# BrauV2_AnalogueInput.net
KiCad netlist of a schematic drawn in Altium Designer
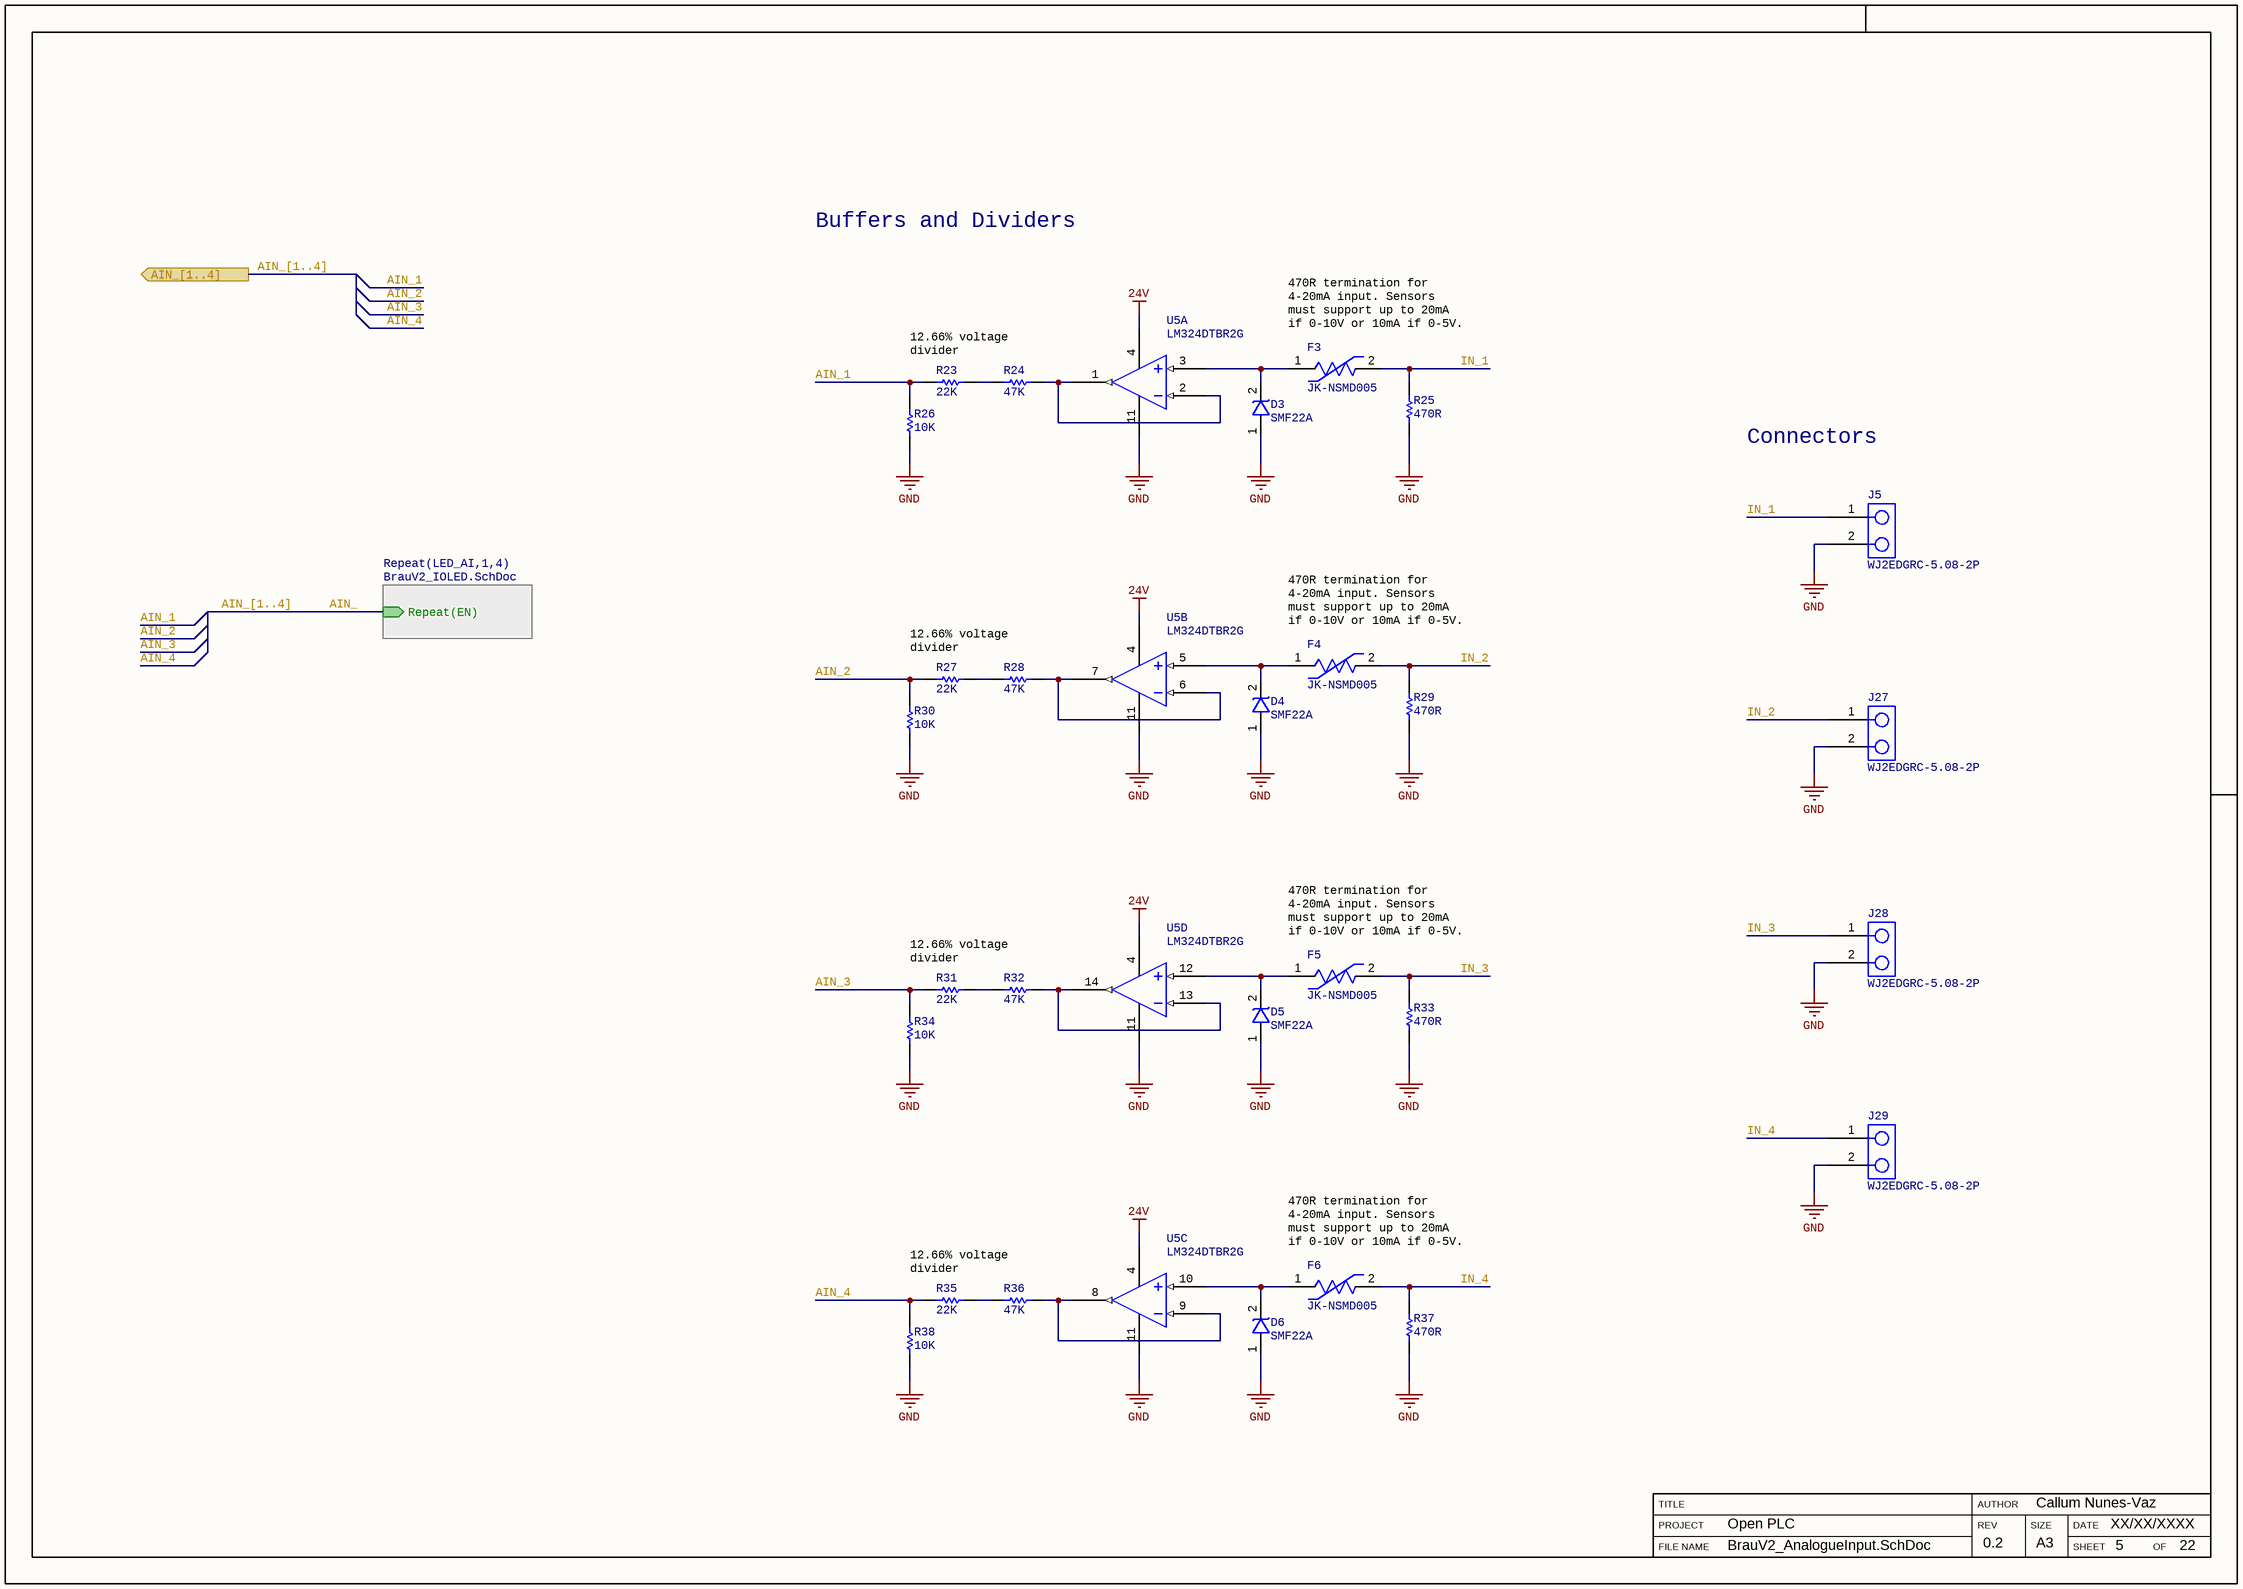
[diagram p0: BrauV2_AnalogueInput.SchDoc]

(export (version "E")
  (design (tool "Eeschema 10.0.6"))
  (components
    (comp (ref "D3")
      (value "SMF22A")
      (footprint "SOD-123FL")
      (description "Unidirectional 22V 24.4V 35.5V 5.6A SOD-123F TVS RoHS")
      (libsource (lib "BrauV2") (part "SMF22A"))
    )
    (comp (ref "D4")
      (value "SMF22A")
      (footprint "SOD-123FL")
      (description "Unidirectional 22V 24.4V 35.5V 5.6A SOD-123F TVS RoHS")
      (libsource (lib "BrauV2") (part "SMF22A"))
    )
    (comp (ref "D5")
      (value "SMF22A")
      (footprint "SOD-123FL")
      (description "Unidirectional 22V 24.4V 35.5V 5.6A SOD-123F TVS RoHS")
      (libsource (lib "BrauV2") (part "SMF22A"))
    )
    (comp (ref "D6")
      (value "SMF22A")
      (footprint "SOD-123FL")
      (description "Unidirectional 22V 24.4V 35.5V 5.6A SOD-123F TVS RoHS")
      (libsource (lib "BrauV2") (part "SMF22A"))
    )
    (comp (ref "F3")
      (value "JK-NSMD005")
      (footprint "SMD_RES_1206(3216)_N")
      (description "60V 150mA 1.5s 1206 PTC Resettable Fuses RoHS")
      (libsource (lib "BrauV2_Resistor") (part "JK-NSMD005"))
    )
    (comp (ref "F4")
      (value "JK-NSMD005")
      (footprint "SMD_RES_1206(3216)_N")
      (description "60V 150mA 1.5s 1206 PTC Resettable Fuses RoHS")
      (libsource (lib "BrauV2_Resistor") (part "JK-NSMD005"))
    )
    (comp (ref "F5")
      (value "JK-NSMD005")
      (footprint "SMD_RES_1206(3216)_N")
      (description "60V 150mA 1.5s 1206 PTC Resettable Fuses RoHS")
      (libsource (lib "BrauV2_Resistor") (part "JK-NSMD005"))
    )
    (comp (ref "F6")
      (value "JK-NSMD005")
      (footprint "SMD_RES_1206(3216)_N")
      (description "60V 150mA 1.5s 1206 PTC Resettable Fuses RoHS")
      (libsource (lib "BrauV2_Resistor") (part "JK-NSMD005"))
    )
    (comp (ref "J5")
      (value "WJ2EDGRC-5.08-2P")
      (footprint "796638-2")
      (description "Covered（4Sided） 2 1 0.200\"（5.08mm） 2 P=5.08mm Pluggable System Terminal Block RoHS")
      (libsource (lib "BrauV2_Connector") (part "WJ2EDGRC-5.08-2P"))
    )
    (comp (ref "J27")
      (value "WJ2EDGRC-5.08-2P")
      (footprint "796638-2")
      (description "Covered（4Sided） 2 1 0.200\"（5.08mm） 2 P=5.08mm Pluggable System Terminal Block RoHS")
      (libsource (lib "BrauV2_Connector") (part "WJ2EDGRC-5.08-2P"))
    )
    (comp (ref "J28")
      (value "WJ2EDGRC-5.08-2P")
      (footprint "796638-2")
      (description "Covered（4Sided） 2 1 0.200\"（5.08mm） 2 P=5.08mm Pluggable System Terminal Block RoHS")
      (libsource (lib "BrauV2_Connector") (part "WJ2EDGRC-5.08-2P"))
    )
    (comp (ref "J29")
      (value "WJ2EDGRC-5.08-2P")
      (footprint "796638-2")
      (description "Covered（4Sided） 2 1 0.200\"（5.08mm） 2 P=5.08mm Pluggable System Terminal Block RoHS")
      (libsource (lib "BrauV2_Connector") (part "WJ2EDGRC-5.08-2P"))
    )
    (comp (ref "R23")
      (value "RC0402FR-0722KL")
      (footprint "SMD_RES_0402(1005)_N")
      (description "22kΩ ±1% 1/16W ±100ppm/℃ 0402 Chip Resistor - Surface Mount RoHS")
      (fields (field (name "TOLERANCE") "1%") (field (name "RESISTANCE") "22K"))
      (libsource (lib "BrauV2_Resistor") (part "22K 0402 1% 1/16W"))
    )
    (comp (ref "R24")
      (value "RC0402FR-0747KL")
      (footprint "SMD_RES_0402(1005)_N")
      (description "47kΩ ±1% 1/16W ±100ppm/℃ 0402 Chip Resistor - Surface Mount RoHS")
      (fields (field (name "TOLERANCE") "1%") (field (name "RESISTANCE") "47K"))
      (libsource (lib "BrauV2_Resistor") (part "47K 0402 1% 1/16W"))
    )
    (comp (ref "R25")
      (value "AC2512FK-07470RL")
      (footprint "SMD_RES_2512(6432)_N")
      (description "470Ω ±1% 1W ±100ppm/℃ 2512 Chip Resistor - Surface Mount RoHS")
      (fields (field (name "TOLERANCE") "1%") (field (name "RESISTANCE") "470R"))
      (libsource (lib "BrauV2_Resistor") (part "470R 2512 1% 1W"))
    )
    (comp (ref "R26")
      (value "RC0402FR-0710KL")
      (footprint "SMD_RES_0402(1005)_N")
      (description "10kΩ ±1% 1/16W ±100ppm/℃ 0402 Chip Resistor - Surface Mount RoHS")
      (fields (field (name "TOLERANCE") "1%") (field (name "RESISTANCE") "10K"))
      (libsource (lib "BrauV2_Resistor") (part "10K 0402 1% 1/16W"))
    )
    (comp (ref "R27")
      (value "RC0402FR-0722KL")
      (footprint "SMD_RES_0402(1005)_N")
      (description "22kΩ ±1% 1/16W ±100ppm/℃ 0402 Chip Resistor - Surface Mount RoHS")
      (fields (field (name "TOLERANCE") "1%") (field (name "RESISTANCE") "22K"))
      (libsource (lib "BrauV2_Resistor") (part "22K 0402 1% 1/16W"))
    )
    (comp (ref "R28")
      (value "RC0402FR-0747KL")
      (footprint "SMD_RES_0402(1005)_N")
      (description "47kΩ ±1% 1/16W ±100ppm/℃ 0402 Chip Resistor - Surface Mount RoHS")
      (fields (field (name "TOLERANCE") "1%") (field (name "RESISTANCE") "47K"))
      (libsource (lib "BrauV2_Resistor") (part "47K 0402 1% 1/16W"))
    )
    (comp (ref "R29")
      (value "AC2512FK-07470RL")
      (footprint "SMD_RES_2512(6432)_N")
      (description "470Ω ±1% 1W ±100ppm/℃ 2512 Chip Resistor - Surface Mount RoHS")
      (fields (field (name "TOLERANCE") "1%") (field (name "RESISTANCE") "470R"))
      (libsource (lib "BrauV2_Resistor") (part "470R 2512 1% 1W"))
    )
    (comp (ref "R30")
      (value "RC0402FR-0710KL")
      (footprint "SMD_RES_0402(1005)_N")
      (description "10kΩ ±1% 1/16W ±100ppm/℃ 0402 Chip Resistor - Surface Mount RoHS")
      (fields (field (name "TOLERANCE") "1%") (field (name "RESISTANCE") "10K"))
      (libsource (lib "BrauV2_Resistor") (part "10K 0402 1% 1/16W"))
    )
    (comp (ref "R31")
      (value "RC0402FR-0722KL")
      (footprint "SMD_RES_0402(1005)_N")
      (description "22kΩ ±1% 1/16W ±100ppm/℃ 0402 Chip Resistor - Surface Mount RoHS")
      (fields (field (name "TOLERANCE") "1%") (field (name "RESISTANCE") "22K"))
      (libsource (lib "BrauV2_Resistor") (part "22K 0402 1% 1/16W"))
    )
    (comp (ref "R32")
      (value "RC0402FR-0747KL")
      (footprint "SMD_RES_0402(1005)_N")
      (description "47kΩ ±1% 1/16W ±100ppm/℃ 0402 Chip Resistor - Surface Mount RoHS")
      (fields (field (name "TOLERANCE") "1%") (field (name "RESISTANCE") "47K"))
      (libsource (lib "BrauV2_Resistor") (part "47K 0402 1% 1/16W"))
    )
    (comp (ref "R33")
      (value "AC2512FK-07470RL")
      (footprint "SMD_RES_2512(6432)_N")
      (description "470Ω ±1% 1W ±100ppm/℃ 2512 Chip Resistor - Surface Mount RoHS")
      (fields (field (name "TOLERANCE") "1%") (field (name "RESISTANCE") "470R"))
      (libsource (lib "BrauV2_Resistor") (part "470R 2512 1% 1W"))
    )
    (comp (ref "R34")
      (value "RC0402FR-0710KL")
      (footprint "SMD_RES_0402(1005)_N")
      (description "10kΩ ±1% 1/16W ±100ppm/℃ 0402 Chip Resistor - Surface Mount RoHS")
      (fields (field (name "TOLERANCE") "1%") (field (name "RESISTANCE") "10K"))
      (libsource (lib "BrauV2_Resistor") (part "10K 0402 1% 1/16W"))
    )
    (comp (ref "R35")
      (value "RC0402FR-0722KL")
      (footprint "SMD_RES_0402(1005)_N")
      (description "22kΩ ±1% 1/16W ±100ppm/℃ 0402 Chip Resistor - Surface Mount RoHS")
      (fields (field (name "TOLERANCE") "1%") (field (name "RESISTANCE") "22K"))
      (libsource (lib "BrauV2_Resistor") (part "22K 0402 1% 1/16W"))
    )
    (comp (ref "R36")
      (value "RC0402FR-0747KL")
      (footprint "SMD_RES_0402(1005)_N")
      (description "47kΩ ±1% 1/16W ±100ppm/℃ 0402 Chip Resistor - Surface Mount RoHS")
      (fields (field (name "TOLERANCE") "1%") (field (name "RESISTANCE") "47K"))
      (libsource (lib "BrauV2_Resistor") (part "47K 0402 1% 1/16W"))
    )
    (comp (ref "R37")
      (value "AC2512FK-07470RL")
      (footprint "SMD_RES_2512(6432)_N")
      (description "470Ω ±1% 1W ±100ppm/℃ 2512 Chip Resistor - Surface Mount RoHS")
      (fields (field (name "TOLERANCE") "1%") (field (name "RESISTANCE") "470R"))
      (libsource (lib "BrauV2_Resistor") (part "470R 2512 1% 1W"))
    )
    (comp (ref "R38")
      (value "RC0402FR-0710KL")
      (footprint "SMD_RES_0402(1005)_N")
      (description "10kΩ ±1% 1/16W ±100ppm/℃ 0402 Chip Resistor - Surface Mount RoHS")
      (fields (field (name "TOLERANCE") "1%") (field (name "RESISTANCE") "10K"))
      (libsource (lib "BrauV2_Resistor") (part "10K 0402 1% 1/16W"))
    )
    (comp (ref "U5")
      (value "LM324DTBR2G")
      (footprint "TSSOP-14")
      (description "General Purpose 4 3V ~ 32V, ±1.5V ~ 16V 1MHz 0.6 V/us TSSOP-14 Operational Amplifiers RoHS")
      (libsource (lib "BrauV2_IC") (part "LM324DTBR2G"))
    )
  )
  (nets
    (net (code "2") (name "/AIN_1") (class "Default")
      (node (ref "R23") (pin "1") (pinfunction "1_1") (pintype "passive"))
      (node (ref "R26") (pin "1") (pinfunction "1_1") (pintype "passive"))
    )
    (net (code "3") (name "/AIN_2") (class "Default")
      (node (ref "R27") (pin "1") (pinfunction "1_1") (pintype "passive"))
      (node (ref "R30") (pin "1") (pinfunction "1_1") (pintype "passive"))
    )
    (net (code "4") (name "/AIN_3") (class "Default")
      (node (ref "R31") (pin "1") (pinfunction "1_1") (pintype "passive"))
      (node (ref "R34") (pin "1") (pinfunction "1_1") (pintype "passive"))
    )
    (net (code "5") (name "/AIN_4") (class "Default")
      (node (ref "R35") (pin "1") (pinfunction "1_1") (pintype "passive"))
      (node (ref "R38") (pin "1") (pinfunction "1_1") (pintype "passive"))
    )
    (net (code "7") (name "/IN_1") (class "Default")
      (node (ref "F3") (pin "2") (pinfunction "2_2") (pintype "passive"))
      (node (ref "J5") (pin "1") (pinfunction "1_1") (pintype "passive"))
      (node (ref "R25") (pin "2") (pinfunction "2_2") (pintype "passive"))
    )
    (net (code "8") (name "/IN_2") (class "Default")
      (node (ref "F4") (pin "2") (pinfunction "2_2") (pintype "passive"))
      (node (ref "J27") (pin "1") (pinfunction "1_1") (pintype "passive"))
      (node (ref "R29") (pin "2") (pinfunction "2_2") (pintype "passive"))
    )
    (net (code "9") (name "/IN_3") (class "Default")
      (node (ref "F5") (pin "2") (pinfunction "2_2") (pintype "passive"))
      (node (ref "J28") (pin "1") (pinfunction "1_1") (pintype "passive"))
      (node (ref "R33") (pin "2") (pinfunction "2_2") (pintype "passive"))
    )
    (net (code "10") (name "/IN_4") (class "Default")
      (node (ref "F6") (pin "2") (pinfunction "2_2") (pintype "passive"))
      (node (ref "J29") (pin "1") (pinfunction "1_1") (pintype "passive"))
      (node (ref "R37") (pin "2") (pinfunction "2_2") (pintype "passive"))
    )
    (net (code "11") (name "24V") (class "Default")
      (node (ref "U5") (pin "4") (pinfunction "VDD_4") (pintype "power_in"))
    )
    (net (code "12") (name "GND") (class "Default")
      (node (ref "D3") (pin "1") (pinfunction "ANODE_1") (pintype "passive"))
      (node (ref "D4") (pin "1") (pinfunction "ANODE_1") (pintype "passive"))
      (node (ref "D5") (pin "1") (pinfunction "ANODE_1") (pintype "passive"))
      (node (ref "D6") (pin "1") (pinfunction "ANODE_1") (pintype "passive"))
      (node (ref "J27") (pin "2") (pinfunction "2_2") (pintype "passive"))
      (node (ref "J28") (pin "2") (pinfunction "2_2") (pintype "passive"))
      (node (ref "J29") (pin "2") (pinfunction "2_2") (pintype "passive"))
      (node (ref "J5") (pin "2") (pinfunction "2_2") (pintype "passive"))
      (node (ref "R25") (pin "1") (pinfunction "1_1") (pintype "passive"))
      (node (ref "R26") (pin "2") (pinfunction "2_2") (pintype "passive"))
      (node (ref "R29") (pin "1") (pinfunction "1_1") (pintype "passive"))
      (node (ref "R30") (pin "2") (pinfunction "2_2") (pintype "passive"))
      (node (ref "R33") (pin "1") (pinfunction "1_1") (pintype "passive"))
      (node (ref "R34") (pin "2") (pinfunction "2_2") (pintype "passive"))
      (node (ref "R37") (pin "1") (pinfunction "1_1") (pintype "passive"))
      (node (ref "R38") (pin "2") (pinfunction "2_2") (pintype "passive"))
      (node (ref "U5") (pin "11") (pinfunction "VSS_11") (pintype "power_in"))
    )
    (net (code "13") (name "Net-(D3-CATHODE)") (class "Default")
      (node (ref "D3") (pin "2") (pinfunction "CATHODE_2") (pintype "passive"))
      (node (ref "F3") (pin "1") (pinfunction "1_1") (pintype "passive"))
      (node (ref "U5") (pin "3") (pinfunction "VIN+_3") (pintype "input"))
    )
    (net (code "14") (name "Net-(D4-CATHODE)") (class "Default")
      (node (ref "D4") (pin "2") (pinfunction "CATHODE_2") (pintype "passive"))
      (node (ref "F4") (pin "1") (pinfunction "1_1") (pintype "passive"))
      (node (ref "U5") (pin "5") (pinfunction "VIN+_5") (pintype "input"))
    )
    (net (code "15") (name "Net-(D5-CATHODE)") (class "Default")
      (node (ref "D5") (pin "2") (pinfunction "CATHODE_2") (pintype "passive"))
      (node (ref "F5") (pin "1") (pinfunction "1_1") (pintype "passive"))
      (node (ref "U5") (pin "12") (pinfunction "VIN+_12") (pintype "input"))
    )
    (net (code "16") (name "Net-(D6-CATHODE)") (class "Default")
      (node (ref "D6") (pin "2") (pinfunction "CATHODE_2") (pintype "passive"))
      (node (ref "F6") (pin "1") (pinfunction "1_1") (pintype "passive"))
      (node (ref "U5") (pin "10") (pinfunction "VIN+_10") (pintype "input"))
    )
    (net (code "17") (name "Net-(R23-Pad2)") (class "Default")
      (node (ref "R23") (pin "2") (pinfunction "2_2") (pintype "passive"))
      (node (ref "R24") (pin "2") (pinfunction "2_2") (pintype "passive"))
    )
    (net (code "18") (name "Net-(R27-Pad2)") (class "Default")
      (node (ref "R27") (pin "2") (pinfunction "2_2") (pintype "passive"))
      (node (ref "R28") (pin "2") (pinfunction "2_2") (pintype "passive"))
    )
    (net (code "19") (name "Net-(R31-Pad2)") (class "Default")
      (node (ref "R31") (pin "2") (pinfunction "2_2") (pintype "passive"))
      (node (ref "R32") (pin "2") (pinfunction "2_2") (pintype "passive"))
    )
    (net (code "20") (name "Net-(R35-Pad2)") (class "Default")
      (node (ref "R35") (pin "2") (pinfunction "2_2") (pintype "passive"))
      (node (ref "R36") (pin "2") (pinfunction "2_2") (pintype "passive"))
    )
    (net (code "21") (name "Net-(U5A-VIN-)") (class "Default")
      (node (ref "R24") (pin "1") (pinfunction "1_1") (pintype "passive"))
      (node (ref "U5") (pin "1") (pinfunction "VOUT_1") (pintype "output"))
      (node (ref "U5") (pin "2") (pinfunction "VIN-_2") (pintype "input"))
    )
    (net (code "22") (name "Net-(U5B-VIN-)") (class "Default")
      (node (ref "R28") (pin "1") (pinfunction "1_1") (pintype "passive"))
      (node (ref "U5") (pin "6") (pinfunction "VIN-_6") (pintype "input"))
      (node (ref "U5") (pin "7") (pinfunction "VOUT_7") (pintype "output"))
    )
    (net (code "23") (name "Net-(U5C-VIN-)") (class "Default")
      (node (ref "R36") (pin "1") (pinfunction "1_1") (pintype "passive"))
      (node (ref "U5") (pin "8") (pinfunction "VOUT_8") (pintype "output"))
      (node (ref "U5") (pin "9") (pinfunction "VIN-_9") (pintype "input"))
    )
    (net (code "24") (name "Net-(U5D-VIN-)") (class "Default")
      (node (ref "R32") (pin "1") (pinfunction "1_1") (pintype "passive"))
      (node (ref "U5") (pin "13") (pinfunction "VIN-_13") (pintype "input"))
      (node (ref "U5") (pin "14") (pinfunction "VOUT_14") (pintype "output"))
    )
  )
)
